# XWiFi.net
KiCad netlist of a schematic drawn in EAGLE
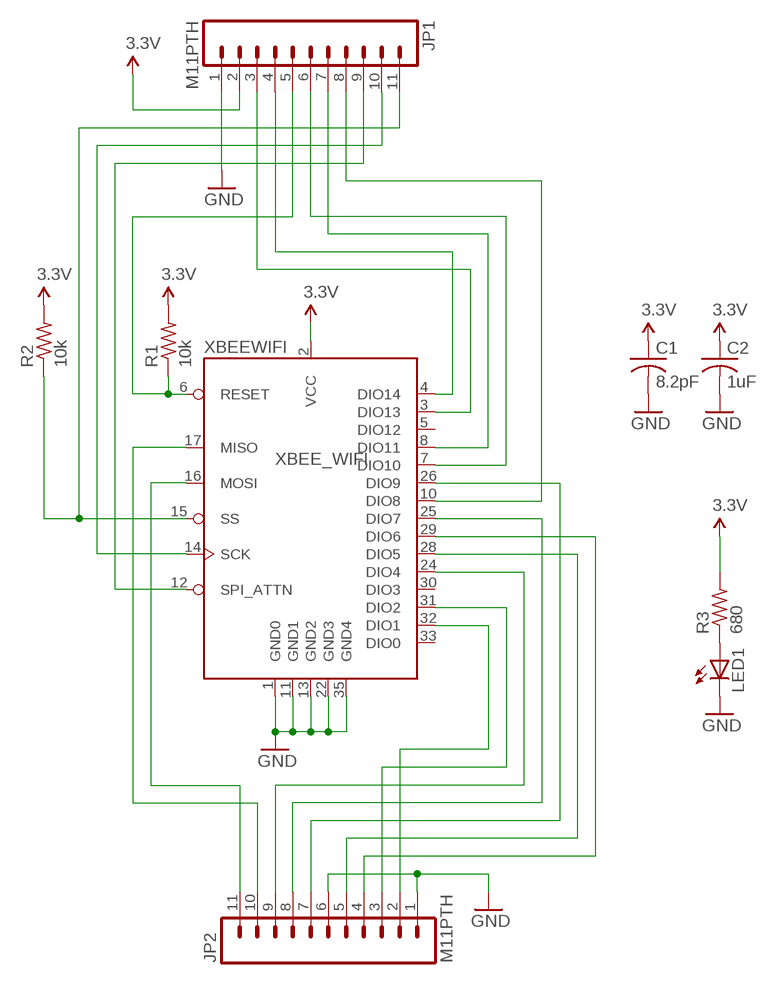
[diagram p0: schematic, sheet 1]

(export (version "E")
  (design (tool "Eeschema 10.0.6"))
  (components
    (comp (ref "C1")
      (value "8.2pF")
      (footprint "eagle-import:0603_RESISTOR")
      (libsource (lib "eagle-import") (part "0603_CAP"))
    )
    (comp (ref "C2")
      (value "1uF")
      (footprint "eagle-import:0603_RESISTOR")
      (libsource (lib "eagle-import") (part "0603_CAP"))
    )
    (comp (ref "JP1")
      (value "M11PTH")
      (footprint "eagle-import:1X11")
      (libsource (lib "eagle-import") (part "M11PTH"))
    )
    (comp (ref "JP2")
      (value "M11PTH")
      (footprint "eagle-import:1X11")
      (libsource (lib "eagle-import") (part "M11PTH"))
    )
    (comp (ref "LED1")
      (value "LEDCHIP-LED0603")
      (footprint "eagle-import:CHIP-LED0603")
      (libsource (lib "eagle-import") (part "LEDCHIP-LED0603"))
    )
    (comp (ref "R1")
      (value "10k")
      (footprint "eagle-import:0603_RESISTOR")
      (libsource (lib "eagle-import") (part "0603_RESISTOR"))
    )
    (comp (ref "R2")
      (value "10k")
      (footprint "eagle-import:0603_RESISTOR")
      (libsource (lib "eagle-import") (part "0603_RESISTOR"))
    )
    (comp (ref "R3")
      (value "680")
      (footprint "eagle-import:0603_RESISTOR")
      (libsource (lib "eagle-import") (part "0603_RESISTOR"))
    )
    (comp (ref "XBEEWIFI")
      (value "XBEE_WIFI")
      (footprint "eagle-import:XBEE_WIFI")
      (libsource (lib "eagle-import") (part "XBEE_WIFI"))
    )
  )
  (nets
    (net (code "1") (name "3.3V") (class "Default")
      (node (ref "C1") (pin "1") (pinfunction "1_1") (pintype "passive"))
      (node (ref "C2") (pin "1") (pinfunction "1_1") (pintype "passive"))
      (node (ref "JP1") (pin "2") (pinfunction "2_2") (pintype "passive"))
      (node (ref "R1") (pin "2") (pinfunction "2_2") (pintype "passive"))
      (node (ref "R2") (pin "2") (pinfunction "2_2") (pintype "passive"))
      (node (ref "R3") (pin "2") (pinfunction "2_2") (pintype "passive"))
      (node (ref "XBEEWIFI") (pin "2") (pinfunction "VCC_2") (pintype "power_in"))
    )
    (net (code "2") (name "GND") (class "Default")
      (node (ref "C1") (pin "2") (pinfunction "2_2") (pintype "passive"))
      (node (ref "C2") (pin "2") (pinfunction "2_2") (pintype "passive"))
      (node (ref "JP1") (pin "1") (pinfunction "1_1") (pintype "passive"))
      (node (ref "JP2") (pin "1") (pinfunction "1_1") (pintype "passive"))
      (node (ref "JP2") (pin "6") (pinfunction "6_6") (pintype "passive"))
      (node (ref "LED1") (pin "C") (pinfunction "C_C") (pintype "passive"))
      (node (ref "XBEEWIFI") (pin "1") (pinfunction "GND0_1") (pintype "power_in"))
      (node (ref "XBEEWIFI") (pin "11") (pinfunction "GND1_11") (pintype "power_in"))
      (node (ref "XBEEWIFI") (pin "13") (pinfunction "GND2_13") (pintype "power_in"))
      (node (ref "XBEEWIFI") (pin "22") (pinfunction "GND3_22") (pintype "power_in"))
      (node (ref "XBEEWIFI") (pin "35") (pinfunction "GND4_35") (pintype "power_in"))
    )
    (net (code "3") (name "Net-(LED1-PadA)") (class "Default")
      (node (ref "LED1") (pin "A") (pinfunction "A_A") (pintype "passive"))
      (node (ref "R3") (pin "1") (pinfunction "1_1") (pintype "passive"))
    )
    (net (code "4") (name "Net-(XBEEWIFI-DIO1)") (class "Default")
      (node (ref "JP2") (pin "2") (pinfunction "2_2") (pintype "passive"))
      (node (ref "XBEEWIFI") (pin "32") (pinfunction "DIO1_32") (pintype "bidirectional"))
    )
    (net (code "5") (name "Net-(XBEEWIFI-DIO2)") (class "Default")
      (node (ref "JP2") (pin "3") (pinfunction "3_3") (pintype "passive"))
      (node (ref "XBEEWIFI") (pin "31") (pinfunction "DIO2_31") (pintype "bidirectional"))
    )
    (net (code "6") (name "Net-(XBEEWIFI-DIO4)") (class "Default")
      (node (ref "JP2") (pin "9") (pinfunction "9_9") (pintype "passive"))
      (node (ref "XBEEWIFI") (pin "24") (pinfunction "DIO4_24") (pintype "bidirectional"))
    )
    (net (code "7") (name "Net-(XBEEWIFI-DIO5)") (class "Default")
      (node (ref "JP2") (pin "5") (pinfunction "5_5") (pintype "passive"))
      (node (ref "XBEEWIFI") (pin "28") (pinfunction "DIO5_28") (pintype "bidirectional"))
    )
    (net (code "8") (name "Net-(XBEEWIFI-DIO6)") (class "Default")
      (node (ref "JP2") (pin "4") (pinfunction "4_4") (pintype "passive"))
      (node (ref "XBEEWIFI") (pin "29") (pinfunction "DIO6_29") (pintype "bidirectional"))
    )
    (net (code "9") (name "Net-(XBEEWIFI-DIO7)") (class "Default")
      (node (ref "JP2") (pin "8") (pinfunction "8_8") (pintype "passive"))
      (node (ref "XBEEWIFI") (pin "25") (pinfunction "DIO7_25") (pintype "bidirectional"))
    )
    (net (code "10") (name "Net-(XBEEWIFI-DIO8)") (class "Default")
      (node (ref "JP1") (pin "8") (pinfunction "8_8") (pintype "passive"))
      (node (ref "XBEEWIFI") (pin "10") (pinfunction "DIO8_10") (pintype "bidirectional"))
    )
    (net (code "11") (name "Net-(XBEEWIFI-DIO9)") (class "Default")
      (node (ref "JP2") (pin "7") (pinfunction "7_7") (pintype "passive"))
      (node (ref "XBEEWIFI") (pin "26") (pinfunction "DIO9_26") (pintype "bidirectional"))
    )
    (net (code "12") (name "Net-(XBEEWIFI-DIO10)") (class "Default")
      (node (ref "JP1") (pin "6") (pinfunction "6_6") (pintype "passive"))
      (node (ref "XBEEWIFI") (pin "7") (pinfunction "DIO10_7") (pintype "bidirectional"))
    )
    (net (code "13") (name "Net-(XBEEWIFI-DIO11)") (class "Default")
      (node (ref "JP1") (pin "7") (pinfunction "7_7") (pintype "passive"))
      (node (ref "XBEEWIFI") (pin "8") (pinfunction "DIO11_8") (pintype "bidirectional"))
    )
    (net (code "14") (name "Net-(XBEEWIFI-DIO13)") (class "Default")
      (node (ref "JP1") (pin "3") (pinfunction "3_3") (pintype "passive"))
      (node (ref "XBEEWIFI") (pin "3") (pinfunction "DIO13_3") (pintype "bidirectional"))
    )
    (net (code "15") (name "Net-(XBEEWIFI-DIO14)") (class "Default")
      (node (ref "JP1") (pin "4") (pinfunction "4_4") (pintype "passive"))
      (node (ref "XBEEWIFI") (pin "4") (pinfunction "DIO14_4") (pintype "bidirectional"))
    )
    (net (code "16") (name "Net-(XBEEWIFI-MISO)") (class "Default")
      (node (ref "JP2") (pin "10") (pinfunction "10_10") (pintype "passive"))
      (node (ref "XBEEWIFI") (pin "17") (pinfunction "MISO_17") (pintype "bidirectional"))
    )
    (net (code "17") (name "Net-(XBEEWIFI-MOSI)") (class "Default")
      (node (ref "JP2") (pin "11") (pinfunction "11_11") (pintype "passive"))
      (node (ref "XBEEWIFI") (pin "16") (pinfunction "MOSI_16") (pintype "bidirectional"))
    )
    (net (code "18") (name "Net-(XBEEWIFI-RESET)") (class "Default")
      (node (ref "JP1") (pin "5") (pinfunction "5_5") (pintype "passive"))
      (node (ref "R1") (pin "1") (pinfunction "1_1") (pintype "passive"))
      (node (ref "XBEEWIFI") (pin "6") (pinfunction "RESET_6") (pintype "input"))
    )
    (net (code "19") (name "Net-(XBEEWIFI-SCK)") (class "Default")
      (node (ref "JP1") (pin "10") (pinfunction "10_10") (pintype "passive"))
      (node (ref "XBEEWIFI") (pin "14") (pinfunction "SCK_14") (pintype "bidirectional"))
    )
    (net (code "20") (name "Net-(XBEEWIFI-SPI_ATTN)") (class "Default")
      (node (ref "JP1") (pin "9") (pinfunction "9_9") (pintype "passive"))
      (node (ref "XBEEWIFI") (pin "12") (pinfunction "SPI_ATTN_12") (pintype "output"))
    )
    (net (code "21") (name "Net-(XBEEWIFI-SS)") (class "Default")
      (node (ref "JP1") (pin "11") (pinfunction "11_11") (pintype "passive"))
      (node (ref "R2") (pin "1") (pinfunction "1_1") (pintype "passive"))
      (node (ref "XBEEWIFI") (pin "15") (pinfunction "SS_15") (pintype "bidirectional"))
    )
    (net (code "22") (name "unconnected-(XBEEWIFI-DIO0-Pad33)") (class "Default")
      (node (ref "XBEEWIFI") (pin "33") (pinfunction "DIO0_33") (pintype "bidirectional"))
    )
    (net (code "23") (name "unconnected-(XBEEWIFI-DIO3-Pad30)") (class "Default")
      (node (ref "XBEEWIFI") (pin "30") (pinfunction "DIO3_30") (pintype "bidirectional"))
    )
    (net (code "24") (name "unconnected-(XBEEWIFI-DIO12-Pad5)") (class "Default")
      (node (ref "XBEEWIFI") (pin "5") (pinfunction "DIO12_5") (pintype "bidirectional"))
    )
  )
)
